# POW-REV2.net
KiCad netlist of a schematic drawn in EAGLE
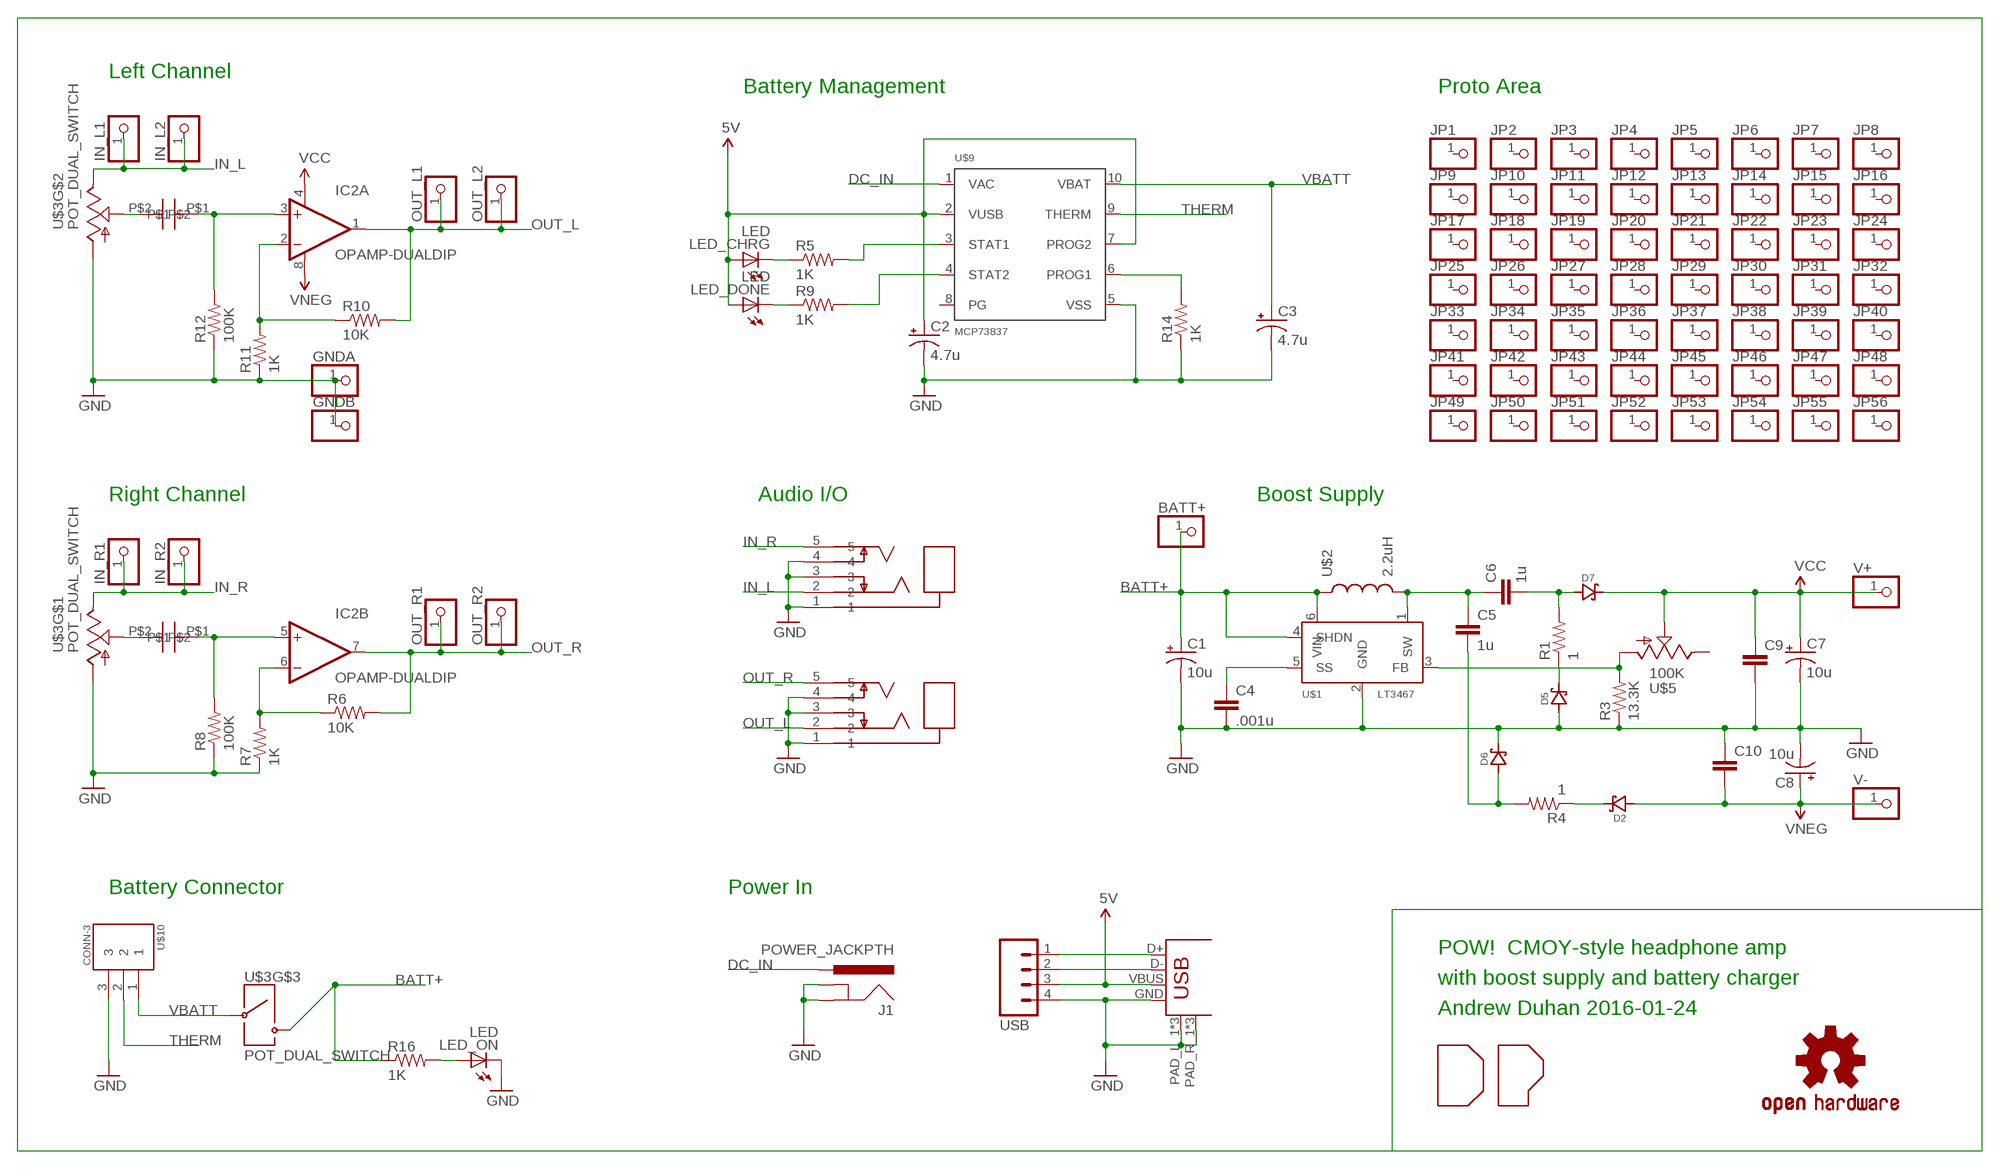
[diagram p0: schematic, sheet 1]

(export (version "E")
  (design (tool "Eeschema 10.0.6"))
  (components
    (comp (ref "BATT+")
      (value "PINHD-1X1CB")
      (footprint "eagle-import:1X01-CLEANBIG")
      (libsource (lib "eagle-import") (part "PINHD-1X1CB"))
    )
    (comp (ref "C1")
      (value "10u")
      (footprint "eagle-import:E2,5-6E")
      (libsource (lib "eagle-import") (part "CPOL-USE2,5-6E"))
    )
    (comp (ref "C2")
      (value "4.7u")
      (footprint "eagle-import:E2,5-6E")
      (libsource (lib "eagle-import") (part "CPOL-USE2,5-6E"))
    )
    (comp (ref "C3")
      (value "4.7u")
      (footprint "eagle-import:E2,5-6E")
      (libsource (lib "eagle-import") (part "CPOL-USE2,5-6E"))
    )
    (comp (ref "C4")
      (value ".001u")
      (footprint "eagle-import:CAP-PTH-SMALL")
      (libsource (lib "eagle-import") (part "CAPPTH"))
    )
    (comp (ref "C5")
      (value "1u")
      (footprint "eagle-import:CAP-PTH-SMALL")
      (libsource (lib "eagle-import") (part "CAPPTH"))
    )
    (comp (ref "C6")
      (value "1u")
      (footprint "eagle-import:CAP-PTH-SMALL")
      (libsource (lib "eagle-import") (part "CAPPTH"))
    )
    (comp (ref "C7")
      (value "10u")
      (footprint "eagle-import:E2,5-6E")
      (libsource (lib "eagle-import") (part "CPOL-USE2,5-6E"))
    )
    (comp (ref "C8")
      (value "10u")
      (footprint "eagle-import:E2,5-6E")
      (libsource (lib "eagle-import") (part "CPOL-USE2,5-6E"))
    )
    (comp (ref "C9")
      (value "CAPPTH")
      (footprint "eagle-import:CAP-PTH-SMALL")
      (libsource (lib "eagle-import") (part "CAPPTH"))
    )
    (comp (ref "C10")
      (value "CAPPTH")
      (footprint "eagle-import:CAP-PTH-SMALL")
      (libsource (lib "eagle-import") (part "CAPPTH"))
    )
    (comp (ref "D2")
      (value "SCHOTTKY")
      (footprint "eagle-import:SOD-123")
      (libsource (lib "eagle-import") (part "SCHOTTKY"))
    )
    (comp (ref "D5")
      (value "SCHOTTKY")
      (footprint "eagle-import:SOD-123")
      (libsource (lib "eagle-import") (part "SCHOTTKY"))
    )
    (comp (ref "D6")
      (value "SCHOTTKY")
      (footprint "eagle-import:SOD-123")
      (libsource (lib "eagle-import") (part "SCHOTTKY"))
    )
    (comp (ref "D7")
      (value "SCHOTTKY")
      (footprint "eagle-import:SOD-123")
      (libsource (lib "eagle-import") (part "SCHOTTKY"))
    )
    (comp (ref "GNDA")
      (value "PINHD-1X1CB")
      (footprint "eagle-import:1X01-CLEANBIG")
      (libsource (lib "eagle-import") (part "PINHD-1X1CB"))
    )
    (comp (ref "GNDB")
      (value "PINHD-1X1CB")
      (footprint "eagle-import:1X01-CLEANBIG")
      (libsource (lib "eagle-import") (part "PINHD-1X1CB"))
    )
    (comp (ref "IC2")
      (value "OPAMP-DUALDIP")
      (footprint "eagle-import:DIP08")
      (libsource (lib "eagle-import") (part "OPAMP-DUALDIP"))
    )
    (comp (ref "IN_JACK")
      (value "JACK_STEREO_SWCUI-SJ1-351X")
      (footprint "eagle-import:AUDIO_JACK-CUI-SJ1-351X")
      (libsource (lib "eagle-import") (part "JACK_STEREO_SWCUI-SJ1-351X"))
    )
    (comp (ref "IN_L1")
      (value "PINHD-1X1CB")
      (footprint "eagle-import:1X01-CLEANBIG")
      (libsource (lib "eagle-import") (part "PINHD-1X1CB"))
    )
    (comp (ref "IN_L2")
      (value "PINHD-1X1CB")
      (footprint "eagle-import:1X01-CLEANBIG")
      (libsource (lib "eagle-import") (part "PINHD-1X1CB"))
    )
    (comp (ref "IN_R1")
      (value "PINHD-1X1CB")
      (footprint "eagle-import:1X01-CLEANBIG")
      (libsource (lib "eagle-import") (part "PINHD-1X1CB"))
    )
    (comp (ref "IN_R2")
      (value "PINHD-1X1CB")
      (footprint "eagle-import:1X01-CLEANBIG")
      (libsource (lib "eagle-import") (part "PINHD-1X1CB"))
    )
    (comp (ref "J1")
      (value "POWER_JACKPTH")
      (footprint "eagle-import:POWER_JACK_PTH")
      (libsource (lib "eagle-import") (part "POWER_JACKPTH"))
    )
    (comp (ref "JP1")
      (value "PINHD-1X1CB")
      (footprint "eagle-import:1X01-CLEANBIG")
      (libsource (lib "eagle-import") (part "PINHD-1X1CB"))
    )
    (comp (ref "JP2")
      (value "PINHD-1X1CB")
      (footprint "eagle-import:1X01-CLEANBIG")
      (libsource (lib "eagle-import") (part "PINHD-1X1CB"))
    )
    (comp (ref "JP3")
      (value "PINHD-1X1CB")
      (footprint "eagle-import:1X01-CLEANBIG")
      (libsource (lib "eagle-import") (part "PINHD-1X1CB"))
    )
    (comp (ref "JP4")
      (value "PINHD-1X1CB")
      (footprint "eagle-import:1X01-CLEANBIG")
      (libsource (lib "eagle-import") (part "PINHD-1X1CB"))
    )
    (comp (ref "JP5")
      (value "PINHD-1X1CB")
      (footprint "eagle-import:1X01-CLEANBIG")
      (libsource (lib "eagle-import") (part "PINHD-1X1CB"))
    )
    (comp (ref "JP6")
      (value "PINHD-1X1CB")
      (footprint "eagle-import:1X01-CLEANBIG")
      (libsource (lib "eagle-import") (part "PINHD-1X1CB"))
    )
    (comp (ref "JP7")
      (value "PINHD-1X1CB")
      (footprint "eagle-import:1X01-CLEANBIG")
      (libsource (lib "eagle-import") (part "PINHD-1X1CB"))
    )
    (comp (ref "JP8")
      (value "PINHD-1X1CB")
      (footprint "eagle-import:1X01-CLEANBIG")
      (libsource (lib "eagle-import") (part "PINHD-1X1CB"))
    )
    (comp (ref "JP9")
      (value "PINHD-1X1CB")
      (footprint "eagle-import:1X01-CLEANBIG")
      (libsource (lib "eagle-import") (part "PINHD-1X1CB"))
    )
    (comp (ref "JP10")
      (value "PINHD-1X1CB")
      (footprint "eagle-import:1X01-CLEANBIG")
      (libsource (lib "eagle-import") (part "PINHD-1X1CB"))
    )
    (comp (ref "JP11")
      (value "PINHD-1X1CB")
      (footprint "eagle-import:1X01-CLEANBIG")
      (libsource (lib "eagle-import") (part "PINHD-1X1CB"))
    )
    (comp (ref "JP12")
      (value "PINHD-1X1CB")
      (footprint "eagle-import:1X01-CLEANBIG")
      (libsource (lib "eagle-import") (part "PINHD-1X1CB"))
    )
    (comp (ref "JP13")
      (value "PINHD-1X1CB")
      (footprint "eagle-import:1X01-CLEANBIG")
      (libsource (lib "eagle-import") (part "PINHD-1X1CB"))
    )
    (comp (ref "JP14")
      (value "PINHD-1X1CB")
      (footprint "eagle-import:1X01-CLEANBIG")
      (libsource (lib "eagle-import") (part "PINHD-1X1CB"))
    )
    (comp (ref "JP15")
      (value "PINHD-1X1CB")
      (footprint "eagle-import:1X01-CLEANBIG")
      (libsource (lib "eagle-import") (part "PINHD-1X1CB"))
    )
    (comp (ref "JP16")
      (value "PINHD-1X1CB")
      (footprint "eagle-import:1X01-CLEANBIG")
      (libsource (lib "eagle-import") (part "PINHD-1X1CB"))
    )
    (comp (ref "JP17")
      (value "PINHD-1X1CB")
      (footprint "eagle-import:1X01-CLEANBIG")
      (libsource (lib "eagle-import") (part "PINHD-1X1CB"))
    )
    (comp (ref "JP18")
      (value "PINHD-1X1CB")
      (footprint "eagle-import:1X01-CLEANBIG")
      (libsource (lib "eagle-import") (part "PINHD-1X1CB"))
    )
    (comp (ref "JP19")
      (value "PINHD-1X1CB")
      (footprint "eagle-import:1X01-CLEANBIG")
      (libsource (lib "eagle-import") (part "PINHD-1X1CB"))
    )
    (comp (ref "JP20")
      (value "PINHD-1X1CB")
      (footprint "eagle-import:1X01-CLEANBIG")
      (libsource (lib "eagle-import") (part "PINHD-1X1CB"))
    )
    (comp (ref "JP21")
      (value "PINHD-1X1CB")
      (footprint "eagle-import:1X01-CLEANBIG")
      (libsource (lib "eagle-import") (part "PINHD-1X1CB"))
    )
    (comp (ref "JP22")
      (value "PINHD-1X1CB")
      (footprint "eagle-import:1X01-CLEANBIG")
      (libsource (lib "eagle-import") (part "PINHD-1X1CB"))
    )
    (comp (ref "JP23")
      (value "PINHD-1X1CB")
      (footprint "eagle-import:1X01-CLEANBIG")
      (libsource (lib "eagle-import") (part "PINHD-1X1CB"))
    )
    (comp (ref "JP24")
      (value "PINHD-1X1CB")
      (footprint "eagle-import:1X01-CLEANBIG")
      (libsource (lib "eagle-import") (part "PINHD-1X1CB"))
    )
    (comp (ref "JP25")
      (value "PINHD-1X1CB")
      (footprint "eagle-import:1X01-CLEANBIG")
      (libsource (lib "eagle-import") (part "PINHD-1X1CB"))
    )
    (comp (ref "JP26")
      (value "PINHD-1X1CB")
      (footprint "eagle-import:1X01-CLEANBIG")
      (libsource (lib "eagle-import") (part "PINHD-1X1CB"))
    )
    (comp (ref "JP27")
      (value "PINHD-1X1CB")
      (footprint "eagle-import:1X01-CLEANBIG")
      (libsource (lib "eagle-import") (part "PINHD-1X1CB"))
    )
    (comp (ref "JP28")
      (value "PINHD-1X1CB")
      (footprint "eagle-import:1X01-CLEANBIG")
      (libsource (lib "eagle-import") (part "PINHD-1X1CB"))
    )
    (comp (ref "JP29")
      (value "PINHD-1X1CB")
      (footprint "eagle-import:1X01-CLEANBIG")
      (libsource (lib "eagle-import") (part "PINHD-1X1CB"))
    )
    (comp (ref "JP30")
      (value "PINHD-1X1CB")
      (footprint "eagle-import:1X01-CLEANBIG")
      (libsource (lib "eagle-import") (part "PINHD-1X1CB"))
    )
    (comp (ref "JP31")
      (value "PINHD-1X1CB")
      (footprint "eagle-import:1X01-CLEANBIG")
      (libsource (lib "eagle-import") (part "PINHD-1X1CB"))
    )
    (comp (ref "JP32")
      (value "PINHD-1X1CB")
      (footprint "eagle-import:1X01-CLEANBIG")
      (libsource (lib "eagle-import") (part "PINHD-1X1CB"))
    )
    (comp (ref "JP33")
      (value "PINHD-1X1CB")
      (footprint "eagle-import:1X01-CLEANBIG")
      (libsource (lib "eagle-import") (part "PINHD-1X1CB"))
    )
    (comp (ref "JP34")
      (value "PINHD-1X1CB")
      (footprint "eagle-import:1X01-CLEANBIG")
      (libsource (lib "eagle-import") (part "PINHD-1X1CB"))
    )
    (comp (ref "JP35")
      (value "PINHD-1X1CB")
      (footprint "eagle-import:1X01-CLEANBIG")
      (libsource (lib "eagle-import") (part "PINHD-1X1CB"))
    )
    (comp (ref "JP36")
      (value "PINHD-1X1CB")
      (footprint "eagle-import:1X01-CLEANBIG")
      (libsource (lib "eagle-import") (part "PINHD-1X1CB"))
    )
    (comp (ref "JP37")
      (value "PINHD-1X1CB")
      (footprint "eagle-import:1X01-CLEANBIG")
      (libsource (lib "eagle-import") (part "PINHD-1X1CB"))
    )
    (comp (ref "JP38")
      (value "PINHD-1X1CB")
      (footprint "eagle-import:1X01-CLEANBIG")
      (libsource (lib "eagle-import") (part "PINHD-1X1CB"))
    )
    (comp (ref "JP39")
      (value "PINHD-1X1CB")
      (footprint "eagle-import:1X01-CLEANBIG")
      (libsource (lib "eagle-import") (part "PINHD-1X1CB"))
    )
    (comp (ref "JP40")
      (value "PINHD-1X1CB")
      (footprint "eagle-import:1X01-CLEANBIG")
      (libsource (lib "eagle-import") (part "PINHD-1X1CB"))
    )
    (comp (ref "JP41")
      (value "PINHD-1X1CB")
      (footprint "eagle-import:1X01-CLEANBIG")
      (libsource (lib "eagle-import") (part "PINHD-1X1CB"))
    )
    (comp (ref "JP42")
      (value "PINHD-1X1CB")
      (footprint "eagle-import:1X01-CLEANBIG")
      (libsource (lib "eagle-import") (part "PINHD-1X1CB"))
    )
    (comp (ref "JP43")
      (value "PINHD-1X1CB")
      (footprint "eagle-import:1X01-CLEANBIG")
      (libsource (lib "eagle-import") (part "PINHD-1X1CB"))
    )
    (comp (ref "JP44")
      (value "PINHD-1X1CB")
      (footprint "eagle-import:1X01-CLEANBIG")
      (libsource (lib "eagle-import") (part "PINHD-1X1CB"))
    )
    (comp (ref "JP45")
      (value "PINHD-1X1CB")
      (footprint "eagle-import:1X01-CLEANBIG")
      (libsource (lib "eagle-import") (part "PINHD-1X1CB"))
    )
    (comp (ref "JP46")
      (value "PINHD-1X1CB")
      (footprint "eagle-import:1X01-CLEANBIG")
      (libsource (lib "eagle-import") (part "PINHD-1X1CB"))
    )
    (comp (ref "JP47")
      (value "PINHD-1X1CB")
      (footprint "eagle-import:1X01-CLEANBIG")
      (libsource (lib "eagle-import") (part "PINHD-1X1CB"))
    )
    (comp (ref "JP48")
      (value "PINHD-1X1CB")
      (footprint "eagle-import:1X01-CLEANBIG")
      (libsource (lib "eagle-import") (part "PINHD-1X1CB"))
    )
    (comp (ref "JP49")
      (value "PINHD-1X1CB")
      (footprint "eagle-import:1X01-CLEANBIG")
      (libsource (lib "eagle-import") (part "PINHD-1X1CB"))
    )
    (comp (ref "JP50")
      (value "PINHD-1X1CB")
      (footprint "eagle-import:1X01-CLEANBIG")
      (libsource (lib "eagle-import") (part "PINHD-1X1CB"))
    )
    (comp (ref "JP51")
      (value "PINHD-1X1CB")
      (footprint "eagle-import:1X01-CLEANBIG")
      (libsource (lib "eagle-import") (part "PINHD-1X1CB"))
    )
    (comp (ref "JP52")
      (value "PINHD-1X1CB")
      (footprint "eagle-import:1X01-CLEANBIG")
      (libsource (lib "eagle-import") (part "PINHD-1X1CB"))
    )
    (comp (ref "JP53")
      (value "PINHD-1X1CB")
      (footprint "eagle-import:1X01-CLEANBIG")
      (libsource (lib "eagle-import") (part "PINHD-1X1CB"))
    )
    (comp (ref "JP54")
      (value "PINHD-1X1CB")
      (footprint "eagle-import:1X01-CLEANBIG")
      (libsource (lib "eagle-import") (part "PINHD-1X1CB"))
    )
    (comp (ref "JP55")
      (value "PINHD-1X1CB")
      (footprint "eagle-import:1X01-CLEANBIG")
      (libsource (lib "eagle-import") (part "PINHD-1X1CB"))
    )
    (comp (ref "JP56")
      (value "PINHD-1X1CB")
      (footprint "eagle-import:1X01-CLEANBIG")
      (libsource (lib "eagle-import") (part "PINHD-1X1CB"))
    )
    (comp (ref "LED_CHRG")
      (value "LED")
      (footprint "eagle-import:SSF-LXH25780ID")
      (libsource (lib "eagle-import") (part "LED"))
    )
    (comp (ref "LED_DONE")
      (value "LED")
      (footprint "eagle-import:SSF-LXH25780ID")
      (libsource (lib "eagle-import") (part "LED"))
    )
    (comp (ref "LED_ON")
      (value "LED")
      (footprint "eagle-import:SSF-LXH25780ID")
      (libsource (lib "eagle-import") (part "LED"))
    )
    (comp (ref "LOGO1")
      (value "OSHW-LOGOS")
      (footprint "eagle-import:OSHW-LOGO-S")
      (libsource (lib "eagle-import") (part "OSHW-LOGOS"))
    )
    (comp (ref "OUT_JACK")
      (value "JACK_STEREO_SWCUI-SJ1-351X")
      (footprint "eagle-import:AUDIO_JACK-CUI-SJ1-351X")
      (libsource (lib "eagle-import") (part "JACK_STEREO_SWCUI-SJ1-351X"))
    )
    (comp (ref "OUT_L1")
      (value "PINHD-1X1CB")
      (footprint "eagle-import:1X01-CLEANBIG")
      (libsource (lib "eagle-import") (part "PINHD-1X1CB"))
    )
    (comp (ref "OUT_L2")
      (value "PINHD-1X1CB")
      (footprint "eagle-import:1X01-CLEANBIG")
      (libsource (lib "eagle-import") (part "PINHD-1X1CB"))
    )
    (comp (ref "OUT_R1")
      (value "PINHD-1X1CB")
      (footprint "eagle-import:1X01-CLEANBIG")
      (libsource (lib "eagle-import") (part "PINHD-1X1CB"))
    )
    (comp (ref "OUT_R2")
      (value "PINHD-1X1CB")
      (footprint "eagle-import:1X01-CLEANBIG")
      (libsource (lib "eagle-import") (part "PINHD-1X1CB"))
    )
    (comp (ref "R1")
      (value "1")
      (footprint "eagle-import:AXIAL-0.3")
      (libsource (lib "eagle-import") (part "RESISTORAXIAL-0.3"))
    )
    (comp (ref "R3")
      (value "13.3K")
      (footprint "eagle-import:AXIAL-0.3")
      (libsource (lib "eagle-import") (part "RESISTORAXIAL-0.3"))
    )
    (comp (ref "R4")
      (value "1")
      (footprint "eagle-import:AXIAL-0.3")
      (libsource (lib "eagle-import") (part "RESISTORAXIAL-0.3"))
    )
    (comp (ref "R5")
      (value "1K")
      (footprint "eagle-import:AXIAL-0.3")
      (libsource (lib "eagle-import") (part "RESISTORAXIAL-0.3"))
    )
    (comp (ref "R6")
      (value "10K")
      (footprint "eagle-import:AXIAL-0.3")
      (libsource (lib "eagle-import") (part "RESISTORAXIAL-0.3"))
    )
    (comp (ref "R7")
      (value "1K")
      (footprint "eagle-import:AXIAL-0.3")
      (libsource (lib "eagle-import") (part "RESISTORAXIAL-0.3"))
    )
    (comp (ref "R8")
      (value "100K")
      (footprint "eagle-import:AXIAL-0.3")
      (libsource (lib "eagle-import") (part "RESISTORAXIAL-0.3"))
    )
    (comp (ref "R9")
      (value "1K")
      (footprint "eagle-import:AXIAL-0.3")
      (libsource (lib "eagle-import") (part "RESISTORAXIAL-0.3"))
    )
    (comp (ref "R10")
      (value "10K")
      (footprint "eagle-import:AXIAL-0.3")
      (libsource (lib "eagle-import") (part "RESISTORAXIAL-0.3"))
    )
    (comp (ref "R11")
      (value "1K")
      (footprint "eagle-import:AXIAL-0.3")
      (libsource (lib "eagle-import") (part "RESISTORAXIAL-0.3"))
    )
    (comp (ref "R12")
      (value "100K")
      (footprint "eagle-import:AXIAL-0.3")
      (libsource (lib "eagle-import") (part "RESISTORAXIAL-0.3"))
    )
    (comp (ref "R14")
      (value "1K")
      (footprint "eagle-import:AXIAL-0.3")
      (libsource (lib "eagle-import") (part "RESISTORAXIAL-0.3"))
    )
    (comp (ref "R16")
      (value "1K")
      (footprint "eagle-import:AXIAL-0.3")
      (libsource (lib "eagle-import") (part "RESISTORAXIAL-0.3"))
    )
    (comp (ref "U$1")
      (value "LT3467")
      (footprint "eagle-import:SOT23-6")
      (libsource (lib "eagle-import") (part "LT3467"))
    )
    (comp (ref "U$2")
      (value "2.2uH")
      (footprint "eagle-import:INDUCTOR_4.5X5")
      (libsource (lib "eagle-import") (part "INDUCTOR-SMD-MED6"))
    )
    (comp (ref "U$3")
      (value "POT_DUAL_SWITCH")
      (footprint "eagle-import:POT_ALPS_RK097")
      (libsource (lib "eagle-import") (part "POT_DUAL_SWITCH"))
    )
    (comp (ref "U$4")
      (value "USB")
      (footprint "eagle-import:USB-MICRO-MOLEX-SMD")
      (libsource (lib "eagle-import") (part "USB"))
    )
    (comp (ref "U$5")
      (value "100K")
      (footprint "eagle-import:TRIM-MURATA-PV36W")
      (libsource (lib "eagle-import") (part "TRIMPOTMURATA"))
    )
    (comp (ref "U$6")
      (value "DP_LOGO")
      (footprint "eagle-import:DP_LOGO")
      (libsource (lib "eagle-import") (part "DP_LOGO"))
    )
    (comp (ref "U$7")
      (value "0.1u")
      (footprint "eagle-import:CAP-MKP_RADIAL")
      (libsource (lib "eagle-import") (part "CAPMKP_RADIAL_7.2X6"))
    )
    (comp (ref "U$8")
      (value "0.1u")
      (footprint "eagle-import:CAP-MKP_RADIAL")
      (libsource (lib "eagle-import") (part "CAPMKP_RADIAL_7.2X6"))
    )
    (comp (ref "U$9")
      (value "MCP73837")
      (footprint "eagle-import:MSOP-10")
      (libsource (lib "eagle-import") (part "MCP73837"))
    )
    (comp (ref "U$10")
      (value "CONN-3")
      (footprint "eagle-import:CONN-0530480310")
      (libsource (lib "eagle-import") (part "CONN-3"))
    )
    (comp (ref "USB")
      (value "M04PTH")
      (footprint "eagle-import:1X04")
      (libsource (lib "eagle-import") (part "M04PTH"))
    )
    (comp (ref "V+")
      (value "PINHD-1X1CB")
      (footprint "eagle-import:1X01-CLEANBIG")
      (libsource (lib "eagle-import") (part "PINHD-1X1CB"))
    )
    (comp (ref "V-")
      (value "PINHD-1X1CB")
      (footprint "eagle-import:1X01-CLEANBIG")
      (libsource (lib "eagle-import") (part "PINHD-1X1CB"))
    )
  )
  (nets
    (net (code "1") (name "/BATT+") (class "Default")
      (node (ref "BATT+") (pin "1") (pinfunction "1_1") (pintype "passive"))
      (node (ref "C1") (pin "+") (pinfunction "+_+") (pintype "passive"))
      (node (ref "R16") (pin "P$1") (pinfunction "1_P$1") (pintype "passive"))
      (node (ref "U$1") (pin "4") (pinfunction "SHDN_4") (pintype "bidirectional"))
      (node (ref "U$1") (pin "6") (pinfunction "VIN_6") (pintype "bidirectional"))
      (node (ref "U$2") (pin "P$1") (pinfunction "1_P$1") (pintype "passive"))
      (node (ref "U$3") (pin "SW1") (pinfunction "1_SW1") (pintype "bidirectional"))
    )
    (net (code "2") (name "/DC_IN") (class "Default")
      (node (ref "J1") (pin "PWR") (pinfunction "PWR_PWR") (pintype "bidirectional"))
      (node (ref "U$9") (pin "1") (pinfunction "VAC_1") (pintype "bidirectional"))
    )
    (net (code "3") (name "/IN_L") (class "Default")
      (node (ref "IN_JACK") (pin "2") (pinfunction "2_2") (pintype "bidirectional"))
      (node (ref "IN_L1") (pin "1") (pinfunction "1_1") (pintype "passive"))
      (node (ref "IN_L2") (pin "1") (pinfunction "1_1") (pintype "passive"))
      (node (ref "U$3") (pin "POT2_B") (pinfunction "B_POT2_B") (pintype "passive"))
    )
    (net (code "4") (name "/IN_R") (class "Default")
      (node (ref "IN_JACK") (pin "5") (pinfunction "5_5") (pintype "bidirectional"))
      (node (ref "IN_R1") (pin "1") (pinfunction "1_1") (pintype "passive"))
      (node (ref "IN_R2") (pin "1") (pinfunction "1_1") (pintype "passive"))
      (node (ref "U$3") (pin "POT1_B") (pinfunction "B_POT1_B") (pintype "passive"))
    )
    (net (code "5") (name "/OUT_L") (class "Default")
      (node (ref "IC2") (pin "1") (pinfunction "OUT_1") (pintype "output"))
      (node (ref "OUT_JACK") (pin "2") (pinfunction "2_2") (pintype "bidirectional"))
      (node (ref "OUT_L1") (pin "1") (pinfunction "1_1") (pintype "passive"))
      (node (ref "OUT_L2") (pin "1") (pinfunction "1_1") (pintype "passive"))
      (node (ref "R10") (pin "P$2") (pinfunction "2_P$2") (pintype "passive"))
    )
    (net (code "6") (name "/OUT_R") (class "Default")
      (node (ref "IC2") (pin "7") (pinfunction "OUT_7") (pintype "output"))
      (node (ref "OUT_JACK") (pin "5") (pinfunction "5_5") (pintype "bidirectional"))
      (node (ref "OUT_R1") (pin "1") (pinfunction "1_1") (pintype "passive"))
      (node (ref "OUT_R2") (pin "1") (pinfunction "1_1") (pintype "passive"))
      (node (ref "R6") (pin "P$2") (pinfunction "2_P$2") (pintype "passive"))
    )
    (net (code "7") (name "/THERM") (class "Default")
      (node (ref "U$10") (pin "2") (pinfunction "2_2") (pintype "bidirectional"))
      (node (ref "U$9") (pin "9") (pinfunction "THERM_9") (pintype "bidirectional"))
    )
    (net (code "8") (name "/VBATT") (class "Default")
      (node (ref "C3") (pin "+") (pinfunction "+_+") (pintype "passive"))
      (node (ref "U$10") (pin "1") (pinfunction "1_1") (pintype "bidirectional"))
      (node (ref "U$3") (pin "SW2") (pinfunction "2_SW2") (pintype "bidirectional"))
      (node (ref "U$9") (pin "10") (pinfunction "VBAT_10") (pintype "bidirectional"))
    )
    (net (code "9") (name "5V") (class "Default")
      (node (ref "C2") (pin "+") (pinfunction "+_+") (pintype "passive"))
      (node (ref "LED_CHRG") (pin "ANODE") (pinfunction "A_ANODE") (pintype "passive"))
      (node (ref "LED_DONE") (pin "ANODE") (pinfunction "A_ANODE") (pintype "passive"))
      (node (ref "U$4") (pin "VBUS") (pinfunction "VBUS_VBUS") (pintype "bidirectional"))
      (node (ref "U$9") (pin "2") (pinfunction "VUSB_2") (pintype "bidirectional"))
      (node (ref "U$9") (pin "7") (pinfunction "PROG2_7") (pintype "bidirectional"))
      (node (ref "USB") (pin "3") (pinfunction "3_3") (pintype "passive"))
    )
    (net (code "10") (name "GND") (class "Default")
      (node (ref "C1") (pin "-") (pinfunction "-_-") (pintype "passive"))
      (node (ref "C10") (pin "1") (pinfunction "1_1") (pintype "passive"))
      (node (ref "C2") (pin "-") (pinfunction "-_-") (pintype "passive"))
      (node (ref "C3") (pin "-") (pinfunction "-_-") (pintype "passive"))
      (node (ref "C4") (pin "2") (pinfunction "2_2") (pintype "passive"))
      (node (ref "C7") (pin "-") (pinfunction "-_-") (pintype "passive"))
      (node (ref "C8") (pin "-") (pinfunction "-_-") (pintype "passive"))
      (node (ref "C9") (pin "2") (pinfunction "2_2") (pintype "passive"))
      (node (ref "D5") (pin "ANODE") (pinfunction "ANODE_ANODE") (pintype "passive"))
      (node (ref "D6") (pin "CATHODE") (pinfunction "CATHODE_CATHODE") (pintype "passive"))
      (node (ref "GNDA") (pin "1") (pinfunction "1_1") (pintype "passive"))
      (node (ref "GNDB") (pin "1") (pinfunction "1_1") (pintype "passive"))
      (node (ref "IN_JACK") (pin "1") (pinfunction "1_1") (pintype "bidirectional"))
      (node (ref "IN_JACK") (pin "3") (pinfunction "3_3") (pintype "bidirectional"))
      (node (ref "IN_JACK") (pin "4") (pinfunction "4_4") (pintype "bidirectional"))
      (node (ref "J1") (pin "GND") (pinfunction "GND_GND") (pintype "bidirectional"))
      (node (ref "J1") (pin "GNDBREAK") (pinfunction "GNDBREAK_GNDBREAK") (pintype "bidirectional"))
      (node (ref "LED_ON") (pin "CATHODE") (pinfunction "C_CATHODE") (pintype "passive"))
      (node (ref "OUT_JACK") (pin "1") (pinfunction "1_1") (pintype "bidirectional"))
      (node (ref "OUT_JACK") (pin "3") (pinfunction "3_3") (pintype "bidirectional"))
      (node (ref "OUT_JACK") (pin "4") (pinfunction "4_4") (pintype "bidirectional"))
      (node (ref "R11") (pin "P$1") (pinfunction "1_P$1") (pintype "passive"))
      (node (ref "R12") (pin "P$1") (pinfunction "1_P$1") (pintype "passive"))
      (node (ref "R14") (pin "P$1") (pinfunction "1_P$1") (pintype "passive"))
      (node (ref "R3") (pin "P$1") (pinfunction "1_P$1") (pintype "passive"))
      (node (ref "R7") (pin "P$1") (pinfunction "1_P$1") (pintype "passive"))
      (node (ref "R8") (pin "P$1") (pinfunction "1_P$1") (pintype "passive"))
      (node (ref "U$1") (pin "2") (pinfunction "GND_2") (pintype "bidirectional"))
      (node (ref "U$10") (pin "3") (pinfunction "3_3") (pintype "bidirectional"))
      (node (ref "U$3") (pin "POT1_A") (pinfunction "A_POT1_A") (pintype "passive"))
      (node (ref "U$3") (pin "POT2_A") (pinfunction "A_POT2_A") (pintype "passive"))
      (node (ref "U$4") (pin "GND") (pinfunction "GND_GND") (pintype "bidirectional"))
      (node (ref "U$4") (pin "PAD_L_1") (pinfunction "P$1_PAD_L_1") (pintype "bidirectional"))
      (node (ref "U$4") (pin "PAD_L_2") (pinfunction "P$1_PAD_L_2") (pintype "bidirectional"))
      (node (ref "U$4") (pin "PAD_L_3") (pinfunction "P$1_PAD_L_3") (pintype "bidirectional"))
      (node (ref "U$4") (pin "PAD_R_1") (pinfunction "P$2_PAD_R_1") (pintype "bidirectional"))
      (node (ref "U$4") (pin "PAD_R_2") (pinfunction "P$2_PAD_R_2") (pintype "bidirectional"))
      (node (ref "U$4") (pin "PAD_R_3") (pinfunction "P$2_PAD_R_3") (pintype "bidirectional"))
      (node (ref "U$9") (pin "5") (pinfunction "VSS_5") (pintype "bidirectional"))
      (node (ref "USB") (pin "4") (pinfunction "4_4") (pintype "passive"))
    )
    (net (code "11") (name "Net-(IC2A-+IN)") (class "Default")
      (node (ref "IC2") (pin "3") (pinfunction "+IN_3") (pintype "input"))
      (node (ref "R12") (pin "P$2") (pinfunction "2_P$2") (pintype "passive"))
      (node (ref "U$8") (pin "P$1") (pinfunction "P$1_P$1") (pintype "bidirectional"))
    )
    (net (code "12") (name "Net-(IC2A--IN)") (class "Default")
      (node (ref "IC2") (pin "2") (pinfunction "-IN_2") (pintype "input"))
      (node (ref "R10") (pin "P$1") (pinfunction "1_P$1") (pintype "passive"))
      (node (ref "R11") (pin "P$2") (pinfunction "2_P$2") (pintype "passive"))
    )
    (net (code "13") (name "Net-(IC2B-+IN)") (class "Default")
      (node (ref "IC2") (pin "5") (pinfunction "+IN_5") (pintype "input"))
      (node (ref "R8") (pin "P$2") (pinfunction "2_P$2") (pintype "passive"))
      (node (ref "U$7") (pin "P$1") (pinfunction "P$1_P$1") (pintype "bidirectional"))
    )
    (net (code "14") (name "Net-(IC2B--IN)") (class "Default")
      (node (ref "IC2") (pin "6") (pinfunction "-IN_6") (pintype "input"))
      (node (ref "R6") (pin "P$1") (pinfunction "1_P$1") (pintype "passive"))
      (node (ref "R7") (pin "P$2") (pinfunction "2_P$2") (pintype "passive"))
    )
    (net (code "15") (name "Net-(LED_CHRG-C)") (class "Default")
      (node (ref "LED_CHRG") (pin "CATHODE") (pinfunction "C_CATHODE") (pintype "passive"))
      (node (ref "R5") (pin "P$1") (pinfunction "1_P$1") (pintype "passive"))
    )
    (net (code "16") (name "Net-(LED_DONE-C)") (class "Default")
      (node (ref "LED_DONE") (pin "CATHODE") (pinfunction "C_CATHODE") (pintype "passive"))
      (node (ref "R9") (pin "P$1") (pinfunction "1_P$1") (pintype "passive"))
    )
    (net (code "17") (name "Net-(LED_ON-A)") (class "Default")
      (node (ref "LED_ON") (pin "ANODE") (pinfunction "A_ANODE") (pintype "passive"))
      (node (ref "R16") (pin "P$2") (pinfunction "2_P$2") (pintype "passive"))
    )
    (net (code "18") (name "Net-(R1-1)") (class "Default")
      (node (ref "D5") (pin "CATHODE") (pinfunction "CATHODE_CATHODE") (pintype "passive"))
      (node (ref "R1") (pin "P$1") (pinfunction "1_P$1") (pintype "passive"))
    )
    (net (code "19") (name "Net-(R1-2)") (class "Default")
      (node (ref "C6") (pin "2") (pinfunction "2_2") (pintype "passive"))
      (node (ref "D7") (pin "ANODE") (pinfunction "ANODE_ANODE") (pintype "passive"))
      (node (ref "R1") (pin "P$2") (pinfunction "2_P$2") (pintype "passive"))
    )
    (net (code "20") (name "Net-(R3-2)") (class "Default")
      (node (ref "R3") (pin "P$2") (pinfunction "2_P$2") (pintype "passive"))
      (node (ref "U$1") (pin "3") (pinfunction "FB_3") (pintype "bidirectional"))
      (node (ref "U$5") (pin "A") (pinfunction "A_A") (pintype "passive"))
    )
    (net (code "21") (name "Net-(R4-1)") (class "Default")
      (node (ref "D2") (pin "CATHODE") (pinfunction "CATHODE_CATHODE") (pintype "passive"))
      (node (ref "R4") (pin "P$1") (pinfunction "1_P$1") (pintype "passive"))
    )
    (net (code "22") (name "Net-(R4-2)") (class "Default")
      (node (ref "C5") (pin "2") (pinfunction "2_2") (pintype "passive"))
      (node (ref "D6") (pin "ANODE") (pinfunction "ANODE_ANODE") (pintype "passive"))
      (node (ref "R4") (pin "P$2") (pinfunction "2_P$2") (pintype "passive"))
    )
    (net (code "23") (name "Net-(R5-2)") (class "Default")
      (node (ref "R5") (pin "P$2") (pinfunction "2_P$2") (pintype "passive"))
      (node (ref "U$9") (pin "3") (pinfunction "STAT1_3") (pintype "bidirectional"))
    )
    (net (code "24") (name "Net-(R9-2)") (class "Default")
      (node (ref "R9") (pin "P$2") (pinfunction "2_P$2") (pintype "passive"))
      (node (ref "U$9") (pin "4") (pinfunction "STAT2_4") (pintype "bidirectional"))
    )
    (net (code "25") (name "Net-(R14-2)") (class "Default")
      (node (ref "R14") (pin "P$2") (pinfunction "2_P$2") (pintype "passive"))
      (node (ref "U$9") (pin "6") (pinfunction "PROG1_6") (pintype "bidirectional"))
    )
    (net (code "26") (name "Net-(U$1-SS)") (class "Default")
      (node (ref "C4") (pin "1") (pinfunction "1_1") (pintype "passive"))
      (node (ref "U$1") (pin "5") (pinfunction "SS_5") (pintype "bidirectional"))
    )
    (net (code "27") (name "Net-(U$1-SW)") (class "Default")
      (node (ref "C5") (pin "1") (pinfunction "1_1") (pintype "passive"))
      (node (ref "C6") (pin "1") (pinfunction "1_1") (pintype "passive"))
      (node (ref "U$1") (pin "1") (pinfunction "SW_1") (pintype "bidirectional"))
      (node (ref "U$2") (pin "P$2") (pinfunction "2_P$2") (pintype "passive"))
    )
    (net (code "28") (name "Net-(U$3A-W)") (class "Default")
      (node (ref "U$3") (pin "POT1_W") (pinfunction "W_POT1_W") (pintype "passive"))
      (node (ref "U$7") (pin "P$2") (pinfunction "P$2_P$2") (pintype "bidirectional"))
    )
    (net (code "29") (name "Net-(U$3B-W)") (class "Default")
      (node (ref "U$3") (pin "POT2_W") (pinfunction "W_POT2_W") (pintype "passive"))
      (node (ref "U$8") (pin "P$2") (pinfunction "P$2_P$2") (pintype "bidirectional"))
    )
    (net (code "30") (name "Net-(U$4-PadD+)") (class "Default")
      (node (ref "U$4") (pin "D+") (pinfunction "D+_D+") (pintype "bidirectional"))
      (node (ref "USB") (pin "1") (pinfunction "1_1") (pintype "passive"))
    )
    (net (code "31") (name "Net-(U$4-PadD-)") (class "Default")
      (node (ref "U$4") (pin "D-") (pinfunction "D-_D-") (pintype "bidirectional"))
      (node (ref "USB") (pin "2") (pinfunction "2_2") (pintype "passive"))
    )
    (net (code "32") (name "VCC") (class "Default")
      (node (ref "C7") (pin "+") (pinfunction "+_+") (pintype "passive"))
      (node (ref "C9") (pin "1") (pinfunction "1_1") (pintype "passive"))
      (node (ref "D7") (pin "CATHODE") (pinfunction "CATHODE_CATHODE") (pintype "passive"))
      (node (ref "IC2") (pin "4") (pinfunction "V-_4") (pintype "power_in"))
      (node (ref "U$5") (pin "W") (pinfunction "W_W") (pintype "passive"))
      (node (ref "V+") (pin "1") (pinfunction "1_1") (pintype "passive"))
    )
    (net (code "33") (name "VNEG") (class "Default")
      (node (ref "C10") (pin "2") (pinfunction "2_2") (pintype "passive"))
      (node (ref "C8") (pin "+") (pinfunction "+_+") (pintype "passive"))
      (node (ref "D2") (pin "ANODE") (pinfunction "ANODE_ANODE") (pintype "passive"))
      (node (ref "IC2") (pin "8") (pinfunction "V+_8") (pintype "power_in"))
      (node (ref "V-") (pin "1") (pinfunction "1_1") (pintype "passive"))
    )
    (net (code "34") (name "unconnected-(JP1-Pad1)") (class "Default")
      (node (ref "JP1") (pin "1") (pinfunction "1_1") (pintype "passive"))
    )
    (net (code "35") (name "unconnected-(JP2-Pad1)") (class "Default")
      (node (ref "JP2") (pin "1") (pinfunction "1_1") (pintype "passive"))
    )
    (net (code "36") (name "unconnected-(JP3-Pad1)") (class "Default")
      (node (ref "JP3") (pin "1") (pinfunction "1_1") (pintype "passive"))
    )
    (net (code "37") (name "unconnected-(JP4-Pad1)") (class "Default")
      (node (ref "JP4") (pin "1") (pinfunction "1_1") (pintype "passive"))
    )
    (net (code "38") (name "unconnected-(JP5-Pad1)") (class "Default")
      (node (ref "JP5") (pin "1") (pinfunction "1_1") (pintype "passive"))
    )
    (net (code "39") (name "unconnected-(JP6-Pad1)") (class "Default")
      (node (ref "JP6") (pin "1") (pinfunction "1_1") (pintype "passive"))
    )
    (net (code "40") (name "unconnected-(JP7-Pad1)") (class "Default")
      (node (ref "JP7") (pin "1") (pinfunction "1_1") (pintype "passive"))
    )
    (net (code "41") (name "unconnected-(JP8-Pad1)") (class "Default")
      (node (ref "JP8") (pin "1") (pinfunction "1_1") (pintype "passive"))
    )
    (net (code "42") (name "unconnected-(JP9-Pad1)") (class "Default")
      (node (ref "JP9") (pin "1") (pinfunction "1_1") (pintype "passive"))
    )
    (net (code "43") (name "unconnected-(JP10-Pad1)") (class "Default")
      (node (ref "JP10") (pin "1") (pinfunction "1_1") (pintype "passive"))
    )
    (net (code "44") (name "unconnected-(JP11-Pad1)") (class "Default")
      (node (ref "JP11") (pin "1") (pinfunction "1_1") (pintype "passive"))
    )
    (net (code "45") (name "unconnected-(JP12-Pad1)") (class "Default")
      (node (ref "JP12") (pin "1") (pinfunction "1_1") (pintype "passive"))
    )
    (net (code "46") (name "unconnected-(JP13-Pad1)") (class "Default")
      (node (ref "JP13") (pin "1") (pinfunction "1_1") (pintype "passive"))
    )
    (net (code "47") (name "unconnected-(JP14-Pad1)") (class "Default")
      (node (ref "JP14") (pin "1") (pinfunction "1_1") (pintype "passive"))
    )
    (net (code "48") (name "unconnected-(JP15-Pad1)") (class "Default")
      (node (ref "JP15") (pin "1") (pinfunction "1_1") (pintype "passive"))
    )
    (net (code "49") (name "unconnected-(JP16-Pad1)") (class "Default")
      (node (ref "JP16") (pin "1") (pinfunction "1_1") (pintype "passive"))
    )
    (net (code "50") (name "unconnected-(JP17-Pad1)") (class "Default")
      (node (ref "JP17") (pin "1") (pinfunction "1_1") (pintype "passive"))
    )
    (net (code "51") (name "unconnected-(JP18-Pad1)") (class "Default")
      (node (ref "JP18") (pin "1") (pinfunction "1_1") (pintype "passive"))
    )
    (net (code "52") (name "unconnected-(JP19-Pad1)") (class "Default")
      (node (ref "JP19") (pin "1") (pinfunction "1_1") (pintype "passive"))
    )
    (net (code "53") (name "unconnected-(JP20-Pad1)") (class "Default")
      (node (ref "JP20") (pin "1") (pinfunction "1_1") (pintype "passive"))
    )
    (net (code "54") (name "unconnected-(JP21-Pad1)") (class "Default")
      (node (ref "JP21") (pin "1") (pinfunction "1_1") (pintype "passive"))
    )
    (net (code "55") (name "unconnected-(JP22-Pad1)") (class "Default")
      (node (ref "JP22") (pin "1") (pinfunction "1_1") (pintype "passive"))
    )
    (net (code "56") (name "unconnected-(JP23-Pad1)") (class "Default")
      (node (ref "JP23") (pin "1") (pinfunction "1_1") (pintype "passive"))
    )
    (net (code "57") (name "unconnected-(JP24-Pad1)") (class "Default")
      (node (ref "JP24") (pin "1") (pinfunction "1_1") (pintype "passive"))
    )
    (net (code "58") (name "unconnected-(JP25-Pad1)") (class "Default")
      (node (ref "JP25") (pin "1") (pinfunction "1_1") (pintype "passive"))
    )
    (net (code "59") (name "unconnected-(JP26-Pad1)") (class "Default")
      (node (ref "JP26") (pin "1") (pinfunction "1_1") (pintype "passive"))
    )
    (net (code "60") (name "unconnected-(JP27-Pad1)") (class "Default")
      (node (ref "JP27") (pin "1") (pinfunction "1_1") (pintype "passive"))
    )
    (net (code "61") (name "unconnected-(JP28-Pad1)") (class "Default")
      (node (ref "JP28") (pin "1") (pinfunction "1_1") (pintype "passive"))
    )
    (net (code "62") (name "unconnected-(JP29-Pad1)") (class "Default")
      (node (ref "JP29") (pin "1") (pinfunction "1_1") (pintype "passive"))
    )
    (net (code "63") (name "unconnected-(JP30-Pad1)") (class "Default")
      (node (ref "JP30") (pin "1") (pinfunction "1_1") (pintype "passive"))
    )
    (net (code "64") (name "unconnected-(JP31-Pad1)") (class "Default")
      (node (ref "JP31") (pin "1") (pinfunction "1_1") (pintype "passive"))
    )
    (net (code "65") (name "unconnected-(JP32-Pad1)") (class "Default")
      (node (ref "JP32") (pin "1") (pinfunction "1_1") (pintype "passive"))
    )
    (net (code "66") (name "unconnected-(JP33-Pad1)") (class "Default")
      (node (ref "JP33") (pin "1") (pinfunction "1_1") (pintype "passive"))
    )
    (net (code "67") (name "unconnected-(JP34-Pad1)") (class "Default")
      (node (ref "JP34") (pin "1") (pinfunction "1_1") (pintype "passive"))
    )
    (net (code "68") (name "unconnected-(JP35-Pad1)") (class "Default")
      (node (ref "JP35") (pin "1") (pinfunction "1_1") (pintype "passive"))
    )
    (net (code "69") (name "unconnected-(JP36-Pad1)") (class "Default")
      (node (ref "JP36") (pin "1") (pinfunction "1_1") (pintype "passive"))
    )
    (net (code "70") (name "unconnected-(JP37-Pad1)") (class "Default")
      (node (ref "JP37") (pin "1") (pinfunction "1_1") (pintype "passive"))
    )
    (net (code "71") (name "unconnected-(JP38-Pad1)") (class "Default")
      (node (ref "JP38") (pin "1") (pinfunction "1_1") (pintype "passive"))
    )
    (net (code "72") (name "unconnected-(JP39-Pad1)") (class "Default")
      (node (ref "JP39") (pin "1") (pinfunction "1_1") (pintype "passive"))
    )
    (net (code "73") (name "unconnected-(JP40-Pad1)") (class "Default")
      (node (ref "JP40") (pin "1") (pinfunction "1_1") (pintype "passive"))
    )
    (net (code "74") (name "unconnected-(JP41-Pad1)") (class "Default")
      (node (ref "JP41") (pin "1") (pinfunction "1_1") (pintype "passive"))
    )
    (net (code "75") (name "unconnected-(JP42-Pad1)") (class "Default")
      (node (ref "JP42") (pin "1") (pinfunction "1_1") (pintype "passive"))
    )
    (net (code "76") (name "unconnected-(JP43-Pad1)") (class "Default")
      (node (ref "JP43") (pin "1") (pinfunction "1_1") (pintype "passive"))
    )
    (net (code "77") (name "unconnected-(JP44-Pad1)") (class "Default")
      (node (ref "JP44") (pin "1") (pinfunction "1_1") (pintype "passive"))
    )
    (net (code "78") (name "unconnected-(JP45-Pad1)") (class "Default")
      (node (ref "JP45") (pin "1") (pinfunction "1_1") (pintype "passive"))
    )
    (net (code "79") (name "unconnected-(JP46-Pad1)") (class "Default")
      (node (ref "JP46") (pin "1") (pinfunction "1_1") (pintype "passive"))
    )
    (net (code "80") (name "unconnected-(JP47-Pad1)") (class "Default")
      (node (ref "JP47") (pin "1") (pinfunction "1_1") (pintype "passive"))
    )
    (net (code "81") (name "unconnected-(JP48-Pad1)") (class "Default")
      (node (ref "JP48") (pin "1") (pinfunction "1_1") (pintype "passive"))
    )
    (net (code "82") (name "unconnected-(JP49-Pad1)") (class "Default")
      (node (ref "JP49") (pin "1") (pinfunction "1_1") (pintype "passive"))
    )
    (net (code "83") (name "unconnected-(JP50-Pad1)") (class "Default")
      (node (ref "JP50") (pin "1") (pinfunction "1_1") (pintype "passive"))
    )
    (net (code "84") (name "unconnected-(JP51-Pad1)") (class "Default")
      (node (ref "JP51") (pin "1") (pinfunction "1_1") (pintype "passive"))
    )
    (net (code "85") (name "unconnected-(JP52-Pad1)") (class "Default")
      (node (ref "JP52") (pin "1") (pinfunction "1_1") (pintype "passive"))
    )
    (net (code "86") (name "unconnected-(JP53-Pad1)") (class "Default")
      (node (ref "JP53") (pin "1") (pinfunction "1_1") (pintype "passive"))
    )
    (net (code "87") (name "unconnected-(JP54-Pad1)") (class "Default")
      (node (ref "JP54") (pin "1") (pinfunction "1_1") (pintype "passive"))
    )
    (net (code "88") (name "unconnected-(JP55-Pad1)") (class "Default")
      (node (ref "JP55") (pin "1") (pinfunction "1_1") (pintype "passive"))
    )
    (net (code "89") (name "unconnected-(JP56-Pad1)") (class "Default")
      (node (ref "JP56") (pin "1") (pinfunction "1_1") (pintype "passive"))
    )
    (net (code "90") (name "unconnected-(U$5-PadB)") (class "Default")
      (node (ref "U$5") (pin "B") (pinfunction "B_B") (pintype "passive"))
    )
    (net (code "91") (name "unconnected-(U$9-PG-Pad8)") (class "Default")
      (node (ref "U$9") (pin "8") (pinfunction "PG_8") (pintype "bidirectional"))
    )
  )
)
